# sch.net
KiCad netlist of a schematic drawn in Altium Designer
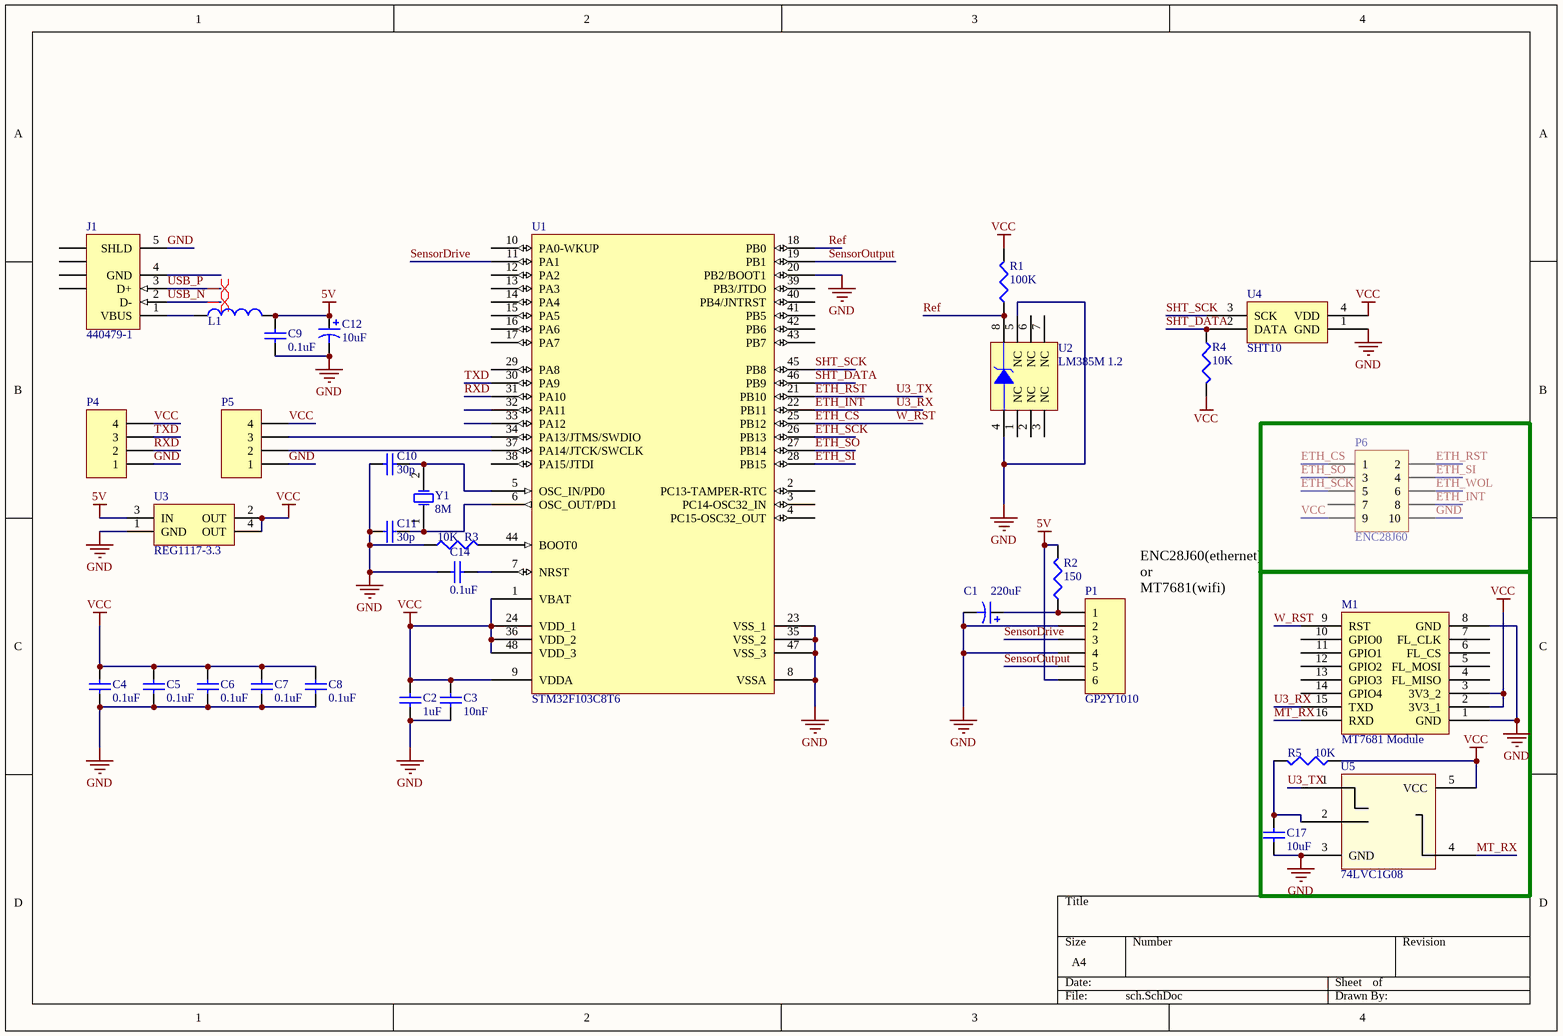
[diagram p0: sch.SchDoc]

(export (version "E")
  (design (tool "Eeschema 10.0.6"))
  (components
    (comp (ref "C1")
      (value "220uF")
      (footprint "B")
      (description "Polarized Capacitor (Radial)")
      (fields (field (name "Comment") "Cap Pol1") (field (name "PUBLISHER") "Altium Limited"))
      (libsource (lib "Miscellaneous Devices") (part "Cap Pol1"))
    )
    (comp (ref "C2")
      (value "1uF")
      (footprint "C1206")
      (description "Capacitor (Semiconductor SIM Model)")
      (fields (field (name "Comment") "Cap Semi") (field (name "PUBLISHER") "Altium Limited"))
      (libsource (lib "Miscellaneous Devices") (part "Cap Semi"))
    )
    (comp (ref "C3")
      (value "10nF")
      (footprint "C1206")
      (description "Capacitor (Semiconductor SIM Model)")
      (fields (field (name "Comment") "Cap Semi") (field (name "PUBLISHER") "Altium Limited"))
      (libsource (lib "Miscellaneous Devices") (part "Cap Semi"))
    )
    (comp (ref "C4")
      (value "0.1uF")
      (footprint "C1206")
      (description "Capacitor (Semiconductor SIM Model)")
      (fields (field (name "Comment") "Cap Semi") (field (name "PUBLISHER") "Altium Limited"))
      (libsource (lib "Miscellaneous Devices") (part "Cap Semi"))
    )
    (comp (ref "C5")
      (value "0.1uF")
      (footprint "C1206")
      (description "Capacitor (Semiconductor SIM Model)")
      (fields (field (name "Comment") "Cap Semi") (field (name "PUBLISHER") "Altium Limited"))
      (libsource (lib "Miscellaneous Devices") (part "Cap Semi"))
    )
    (comp (ref "C6")
      (value "0.1uF")
      (footprint "C1206")
      (description "Capacitor (Semiconductor SIM Model)")
      (fields (field (name "Comment") "Cap Semi") (field (name "PUBLISHER") "Altium Limited"))
      (libsource (lib "Miscellaneous Devices") (part "Cap Semi"))
    )
    (comp (ref "C7")
      (value "0.1uF")
      (footprint "C1206")
      (description "Capacitor (Semiconductor SIM Model)")
      (fields (field (name "Comment") "Cap Semi") (field (name "PUBLISHER") "Altium Limited"))
      (libsource (lib "Miscellaneous Devices") (part "Cap Semi"))
    )
    (comp (ref "C8")
      (value "0.1uF")
      (footprint "C1206")
      (description "Capacitor (Semiconductor SIM Model)")
      (fields (field (name "Comment") "Cap Semi") (field (name "PUBLISHER") "Altium Limited"))
      (libsource (lib "Miscellaneous Devices") (part "Cap Semi"))
    )
    (comp (ref "C9")
      (value "0.1uF")
      (footprint "C1206")
      (description "Capacitor (Semiconductor SIM Model)")
      (fields (field (name "Comment") "Cap Semi") (field (name "PUBLISHER") "Altium Limited"))
      (libsource (lib "Miscellaneous Devices") (part "Cap Semi"))
    )
    (comp (ref "C10")
      (value "30p")
      (footprint "C1206")
      (description "Capacitor (Semiconductor SIM Model)")
      (fields (field (name "Comment") "Cap Semi") (field (name "PUBLISHER") "Altium Limited"))
      (libsource (lib "Miscellaneous Devices") (part "Cap Semi"))
    )
    (comp (ref "C11")
      (value "30p")
      (footprint "C1206")
      (description "Capacitor (Semiconductor SIM Model)")
      (fields (field (name "Comment") "Cap Semi") (field (name "PUBLISHER") "Altium Limited"))
      (libsource (lib "Miscellaneous Devices") (part "Cap Semi"))
    )
    (comp (ref "C12")
      (value "10uF")
      (footprint "1812")
      (description "Polarized Capacitor (Surface Mount)")
      (fields (field (name "Comment") "Cap Pol3") (field (name "PUBLISHER") "Altium Limited"))
      (libsource (lib "Miscellaneous Devices") (part "Cap Pol3"))
    )
    (comp (ref "C14")
      (value "0.1uF")
      (footprint "C1206")
      (description "Capacitor (Semiconductor SIM Model)")
      (fields (field (name "Comment") "Cap Semi") (field (name "PUBLISHER") "Altium Limited"))
      (libsource (lib "Miscellaneous Devices") (part "Cap Semi"))
    )
    (comp (ref "C17")
      (value "10uF")
      (footprint "C1206")
      (description "Capacitor (Semiconductor SIM Model)")
      (fields (field (name "Comment") "Cap Semi") (field (name "PUBLISHER") "Altium Limited"))
      (libsource (lib "Miscellaneous Devices") (part "Cap Semi"))
    )
    (comp (ref "J1")
      (value "440479-1")
      (footprint "440479")
      (description "USB 2.0, Right Angle, SMT, AB Type, Receptacle, 5 Position, Black")
      (fields (field (name "PUBLISHER") "Altium Limited"))
      (libsource (lib "AMP Serial Bus USB") (part "440479-1"))
    )
    (comp (ref "L1")
      (value "Inductor")
      (footprint "2012_Chip")
      (fields (field (name "PUBLISHER") "Altium Limited"))
      (libsource (lib "Miscellaneous Devices") (part "Inductor"))
    )
    (comp (ref "M1") (value "MT7681 Module") (libsource (lib "MT7681_MOD") (part "MT7681")))
    (comp (ref "P1")
      (value "GP2Y1010")
      (footprint "GP2Y1010AU0F")
      (description "Header, 6-Pin")
      (fields (field (name "PUBLISHER") "Altium Limited"))
      (libsource (lib "Miscellaneous Connectors") (part "Header 6"))
    )
    (comp (ref "P4")
      (value "Header 4")
      (footprint "HDR1X4")
      (description "Header, 4-Pin")
      (fields (field (name "PUBLISHER") "Altium Limited"))
      (libsource (lib "Miscellaneous Connectors") (part "Header 4"))
    )
    (comp (ref "P5")
      (value "Header 4")
      (footprint "HDR1X4")
      (description "Header, 4-Pin")
      (fields (field (name "PUBLISHER") "Altium Limited"))
      (libsource (lib "Miscellaneous Connectors") (part "Header 4"))
    )
    (comp (ref "P6")
      (value "ENC28J60")
      (footprint "ENC28J60Board")
      (description "Header, 5-Pin, Dual row")
      (fields (field (name "PUBLISHER") "Altium Limited"))
      (libsource (lib "Miscellaneous Connectors") (part "Header 5X2"))
    )
    (comp (ref "R1")
      (value "100K")
      (footprint "2012[0805]")
      (description "Resistor")
      (fields (field (name "Comment") "Res3") (field (name "PUBLISHER") "Altium Limited"))
      (libsource (lib "Miscellaneous Devices") (part "Res3"))
    )
    (comp (ref "R2")
      (value "150")
      (footprint "2012[0805]")
      (description "Resistor")
      (fields (field (name "Comment") "Res3") (field (name "PUBLISHER") "Altium Limited"))
      (libsource (lib "Miscellaneous Devices") (part "Res3"))
    )
    (comp (ref "R3")
      (value "10K")
      (footprint "2012[0805]")
      (description "Resistor")
      (fields (field (name "Comment") "Res3") (field (name "PUBLISHER") "Altium Limited"))
      (libsource (lib "Miscellaneous Devices") (part "Res3"))
    )
    (comp (ref "R4")
      (value "10K")
      (footprint "2012[0805]")
      (description "Resistor")
      (fields (field (name "Comment") "Res3") (field (name "PUBLISHER") "Altium Limited"))
      (libsource (lib "Miscellaneous Devices") (part "Res3"))
    )
    (comp (ref "R5")
      (value "10K")
      (footprint "2012[0805]")
      (description "Resistor")
      (fields (field (name "Comment") "Res3") (field (name "PUBLISHER") "Altium Limited"))
      (libsource (lib "Miscellaneous Devices") (part "Res3"))
    )
    (comp (ref "U1")
      (value "STM32F103C8T6")
      (footprint "LQFP48_N")
      (description "STM32 ARM-based 32-bit MCU with 64 Kbytes Flash, 48-pin LQFP, Industrial Temperature")
      (fields (field (name "PUBLISHER") "Altium Limited"))
      (libsource (lib "ST Microcontroller 32-Bit STM32") (part "STM32F103C8T6"))
    )
    (comp (ref "U2")
      (value "LM385M 1.2")
      (footprint "D008_N")
      (description "Micropower Voltage Reference")
      (fields (field (name "PUBLISHER") "Altium Limited"))
      (libsource (lib "TI Power Mgt Voltage Reference") (part "LM385D-2.5"))
    )
    (comp (ref "U3")
      (value "REG1117-3.3")
      (footprint "ZZ311")
      (description "800mA and 1A Low Dropout Positive Regulator 2.85V, 3.3V, 5V, and Adjustable")
      (fields (field (name "PUBLISHER") "Altium Limited"))
      (libsource (lib "BB Power Mgt Voltage Regulator") (part "REG1117-3.3"))
    )
    (comp (ref "U4") (value "SHT10") (footprint "SOIC127P600-8N") (libsource (lib "SHT10") (part "SHT10")))
    (comp (ref "U5") (value "74LVC1G08") (libsource (lib "74lvc1g08") (part "74LVC1G08")))
    (comp (ref "Y1")
      (value "8M")
      (footprint "BCY-W2/E4.7")
      (description "Crystal Oscillator")
      (fields (field (name "PUBLISHER") "Altium Limited"))
      (libsource (lib "Miscellaneous Devices") (part "XTAL"))
    )
  )
  (nets
    (net (code "1") (name "/ETH_CS") (class "Default")
      (node (ref "M1") (pin "9") (pinfunction "RST_9") (pintype "passive"))
      (node (ref "P6") (pin "1") (pinfunction "1_1") (pintype "passive"))
      (node (ref "U1") (pin "25") (pinfunction "PB12_25") (pintype "bidirectional"))
    )
    (net (code "2") (name "/ETH_INT") (class "Default")
      (node (ref "M1") (pin "15") (pinfunction "TXD_15") (pintype "passive"))
      (node (ref "P6") (pin "8") (pinfunction "8_8") (pintype "passive"))
      (node (ref "U1") (pin "22") (pinfunction "PB11_22") (pintype "bidirectional"))
    )
    (net (code "3") (name "/ETH_RST") (class "Default")
      (node (ref "P6") (pin "2") (pinfunction "2_2") (pintype "passive"))
      (node (ref "U1") (pin "21") (pinfunction "PB10_21") (pintype "bidirectional"))
      (node (ref "U5") (pin "1") (pinfunction "B_1") (pintype "passive"))
    )
    (net (code "4") (name "/ETH_SCK") (class "Default")
      (node (ref "P6") (pin "5") (pinfunction "5_5") (pintype "passive"))
      (node (ref "U1") (pin "26") (pinfunction "PB13_26") (pintype "bidirectional"))
    )
    (net (code "5") (name "/ETH_SI") (class "Default")
      (node (ref "P6") (pin "4") (pinfunction "4_4") (pintype "passive"))
      (node (ref "U1") (pin "28") (pinfunction "PB15_28") (pintype "bidirectional"))
    )
    (net (code "6") (name "/ETH_SO") (class "Default")
      (node (ref "P6") (pin "3") (pinfunction "3_3") (pintype "passive"))
      (node (ref "U1") (pin "27") (pinfunction "PB14_27") (pintype "bidirectional"))
    )
    (net (code "7") (name "/ETH_WOL") (class "Default")
      (node (ref "P6") (pin "6") (pinfunction "6_6") (pintype "passive"))
    )
    (net (code "8") (name "/MT_RX") (class "Default")
      (node (ref "M1") (pin "16") (pinfunction "RXD_16") (pintype "passive"))
      (node (ref "U5") (pin "4") (pinfunction "Y_4") (pintype "passive"))
    )
    (net (code "9") (name "/RXD") (class "Default")
      (node (ref "P4") (pin "2") (pinfunction "2_2") (pintype "passive"))
      (node (ref "U1") (pin "31") (pinfunction "PA10_31") (pintype "bidirectional"))
    )
    (net (code "10") (name "/Ref") (class "Default")
      (node (ref "R1") (pin "1") (pinfunction "1_1") (pintype "passive"))
      (node (ref "U1") (pin "18") (pinfunction "PB0_18") (pintype "bidirectional"))
      (node (ref "U2") (pin "8") (pinfunction "K_8") (pintype "passive"))
    )
    (net (code "11") (name "/SHT_DATA") (class "Default")
      (node (ref "R4") (pin "1") (pinfunction "1_1") (pintype "passive"))
      (node (ref "U1") (pin "46") (pinfunction "PB9_46") (pintype "bidirectional"))
      (node (ref "U4") (pin "2") (pinfunction "DATA_2") (pintype "passive"))
    )
    (net (code "12") (name "/SHT_SCK") (class "Default")
      (node (ref "U1") (pin "45") (pinfunction "PB8_45") (pintype "bidirectional"))
      (node (ref "U4") (pin "3") (pinfunction "SCK_3") (pintype "passive"))
    )
    (net (code "13") (name "/SensorDrive") (class "Default")
      (node (ref "P1") (pin "3") (pinfunction "3_3") (pintype "passive"))
      (node (ref "U1") (pin "11") (pinfunction "PA1_11") (pintype "bidirectional"))
    )
    (net (code "14") (name "/SensorOutput") (class "Default")
      (node (ref "P1") (pin "5") (pinfunction "5_5") (pintype "passive"))
      (node (ref "U1") (pin "19") (pinfunction "PB1_19") (pintype "bidirectional"))
    )
    (net (code "15") (name "/TXD") (class "Default")
      (node (ref "P4") (pin "3") (pinfunction "3_3") (pintype "passive"))
      (node (ref "U1") (pin "30") (pinfunction "PA9_30") (pintype "bidirectional"))
    )
    (net (code "16") (name "/USB_N") (class "Default")
      (node (ref "J1") (pin "2") (pinfunction "D-_2") (pintype "input"))
    )
    (net (code "17") (name "/USB_P") (class "Default")
      (node (ref "J1") (pin "3") (pinfunction "D+_3") (pintype "input"))
    )
    (net (code "18") (name "5V") (class "Default")
      (node (ref "C12") (pin "1") (pinfunction "1_1") (pintype "passive"))
      (node (ref "C9") (pin "2") (pinfunction "2_2") (pintype "passive"))
      (node (ref "L1") (pin "2") (pinfunction "2_2") (pintype "passive"))
      (node (ref "P1") (pin "6") (pinfunction "6_6") (pintype "passive"))
      (node (ref "R2") (pin "2") (pinfunction "2_2") (pintype "passive"))
      (node (ref "U3") (pin "3") (pinfunction "IN_3") (pintype "power_in"))
    )
    (net (code "19") (name "GND") (class "Default")
      (node (ref "C1") (pin "2") (pinfunction "2_2") (pintype "passive"))
      (node (ref "C10") (pin "2") (pinfunction "2_2") (pintype "passive"))
      (node (ref "C11") (pin "2") (pinfunction "2_2") (pintype "passive"))
      (node (ref "C12") (pin "2") (pinfunction "2_2") (pintype "passive"))
      (node (ref "C14") (pin "2") (pinfunction "2_2") (pintype "passive"))
      (node (ref "C17") (pin "1") (pinfunction "1_1") (pintype "passive"))
      (node (ref "C2") (pin "1") (pinfunction "1_1") (pintype "passive"))
      (node (ref "C3") (pin "1") (pinfunction "1_1") (pintype "passive"))
      (node (ref "C4") (pin "1") (pinfunction "1_1") (pintype "passive"))
      (node (ref "C5") (pin "1") (pinfunction "1_1") (pintype "passive"))
      (node (ref "C6") (pin "1") (pinfunction "1_1") (pintype "passive"))
      (node (ref "C7") (pin "1") (pinfunction "1_1") (pintype "passive"))
      (node (ref "C8") (pin "1") (pinfunction "1_1") (pintype "passive"))
      (node (ref "C9") (pin "1") (pinfunction "1_1") (pintype "passive"))
      (node (ref "J1") (pin "5") (pinfunction "SHLD_5") (pintype "passive"))
      (node (ref "M1") (pin "1") (pinfunction "GND_1") (pintype "passive"))
      (node (ref "M1") (pin "8") (pinfunction "GND_8") (pintype "passive"))
      (node (ref "P1") (pin "2") (pinfunction "2_2") (pintype "passive"))
      (node (ref "P1") (pin "4") (pinfunction "4_4") (pintype "passive"))
      (node (ref "P4") (pin "1") (pinfunction "1_1") (pintype "passive"))
      (node (ref "P5") (pin "1") (pinfunction "1_1") (pintype "passive"))
      (node (ref "P6") (pin "10") (pinfunction "10_10") (pintype "passive"))
      (node (ref "R3") (pin "1") (pinfunction "1_1") (pintype "passive"))
      (node (ref "U1") (pin "20") (pinfunction "PB2/BOOT1_20") (pintype "bidirectional"))
      (node (ref "U1") (pin "23") (pinfunction "VSS_1_23") (pintype "power_in"))
      (node (ref "U1") (pin "35") (pinfunction "VSS_2_35") (pintype "power_in"))
      (node (ref "U1") (pin "47") (pinfunction "VSS_3_47") (pintype "power_in"))
      (node (ref "U1") (pin "8") (pinfunction "VSSA_8") (pintype "power_in"))
      (node (ref "U2") (pin "4") (pinfunction "A_4") (pintype "passive"))
      (node (ref "U2") (pin "5") (pinfunction "NC_5") (pintype "passive"))
      (node (ref "U3") (pin "1") (pinfunction "GND_1") (pintype "power_in"))
      (node (ref "U4") (pin "1") (pinfunction "GND_1") (pintype "passive"))
      (node (ref "U5") (pin "3") (pinfunction "GND_3") (pintype "passive"))
    )
    (net (code "20") (name "Net-(C1-Pad1)") (class "Default")
      (node (ref "C1") (pin "1") (pinfunction "1_1") (pintype "passive"))
      (node (ref "P1") (pin "1") (pinfunction "1_1") (pintype "passive"))
      (node (ref "R2") (pin "1") (pinfunction "1_1") (pintype "passive"))
    )
    (net (code "21") (name "Net-(J1-VBUS)") (class "Default")
      (node (ref "J1") (pin "1") (pinfunction "VBUS_1") (pintype "power_in"))
      (node (ref "L1") (pin "1") (pinfunction "1_1") (pintype "passive"))
    )
    (net (code "22") (name "Net-(U1-BOOT0)") (class "Default")
      (node (ref "R3") (pin "2") (pinfunction "2_2") (pintype "passive"))
      (node (ref "U1") (pin "44") (pinfunction "BOOT0_44") (pintype "input"))
    )
    (net (code "23") (name "Net-(U1-NRST)") (class "Default")
      (node (ref "C14") (pin "1") (pinfunction "1_1") (pintype "passive"))
      (node (ref "U1") (pin "7") (pinfunction "NRST_7") (pintype "bidirectional"))
    )
    (net (code "24") (name "Net-(U1-OSC_IN{slash}PD0)") (class "Default")
      (node (ref "C10") (pin "1") (pinfunction "1_1") (pintype "passive"))
      (node (ref "U1") (pin "5") (pinfunction "OSC_IN/PD0_5") (pintype "input"))
      (node (ref "Y1") (pin "2") (pinfunction "OSC2_2") (pintype "passive"))
    )
    (net (code "25") (name "Net-(U1-OSC_OUT{slash}PD1)") (class "Default")
      (node (ref "C11") (pin "1") (pinfunction "1_1") (pintype "passive"))
      (node (ref "U1") (pin "6") (pinfunction "OSC_OUT/PD1_6") (pintype "output"))
      (node (ref "Y1") (pin "1") (pinfunction "OSC1_1") (pintype "passive"))
    )
    (net (code "26") (name "Net-(U1-PA13{slash}JTMS{slash}SWDIO)") (class "Default")
      (node (ref "P5") (pin "3") (pinfunction "3_3") (pintype "passive"))
      (node (ref "U1") (pin "34") (pinfunction "PA13/JTMS/SWDIO_34") (pintype "bidirectional"))
    )
    (net (code "27") (name "Net-(U1-PA14{slash}JTCK{slash}SWCLK)") (class "Default")
      (node (ref "P5") (pin "2") (pinfunction "2_2") (pintype "passive"))
      (node (ref "U1") (pin "37") (pinfunction "PA14/JTCK/SWCLK_37") (pintype "bidirectional"))
    )
    (net (code "28") (name "Net-(U5-A)") (class "Default")
      (node (ref "C17") (pin "2") (pinfunction "2_2") (pintype "passive"))
      (node (ref "R5") (pin "2") (pinfunction "2_2") (pintype "passive"))
      (node (ref "U5") (pin "2") (pinfunction "A_2") (pintype "passive"))
    )
    (net (code "29") (name "VCC") (class "Default")
      (node (ref "C2") (pin "2") (pinfunction "2_2") (pintype "passive"))
      (node (ref "C3") (pin "2") (pinfunction "2_2") (pintype "passive"))
      (node (ref "C4") (pin "2") (pinfunction "2_2") (pintype "passive"))
      (node (ref "C5") (pin "2") (pinfunction "2_2") (pintype "passive"))
      (node (ref "C6") (pin "2") (pinfunction "2_2") (pintype "passive"))
      (node (ref "C7") (pin "2") (pinfunction "2_2") (pintype "passive"))
      (node (ref "C8") (pin "2") (pinfunction "2_2") (pintype "passive"))
      (node (ref "M1") (pin "2") (pinfunction "3V3_1_2") (pintype "passive"))
      (node (ref "M1") (pin "3") (pinfunction "3V3_2_3") (pintype "passive"))
      (node (ref "P4") (pin "4") (pinfunction "4_4") (pintype "passive"))
      (node (ref "P5") (pin "4") (pinfunction "4_4") (pintype "passive"))
      (node (ref "P6") (pin "9") (pinfunction "9_9") (pintype "passive"))
      (node (ref "R1") (pin "2") (pinfunction "2_2") (pintype "passive"))
      (node (ref "R4") (pin "2") (pinfunction "2_2") (pintype "passive"))
      (node (ref "R5") (pin "1") (pinfunction "1_1") (pintype "passive"))
      (node (ref "U1") (pin "1") (pinfunction "VBAT_1") (pintype "power_in"))
      (node (ref "U1") (pin "24") (pinfunction "VDD_1_24") (pintype "power_in"))
      (node (ref "U1") (pin "36") (pinfunction "VDD_2_36") (pintype "power_in"))
      (node (ref "U1") (pin "48") (pinfunction "VDD_3_48") (pintype "power_in"))
      (node (ref "U1") (pin "9") (pinfunction "VDDA_9") (pintype "power_in"))
      (node (ref "U3") (pin "2") (pinfunction "OUT_2") (pintype "power_in"))
      (node (ref "U3") (pin "4") (pinfunction "OUT_4") (pintype "power_in"))
      (node (ref "U4") (pin "4") (pinfunction "VDD_4") (pintype "passive"))
      (node (ref "U5") (pin "5") (pinfunction "VCC_5") (pintype "passive"))
    )
    (net (code "30") (name "unconnected-(J1-GND-Pad4)") (class "Default")
      (node (ref "J1") (pin "4") (pinfunction "GND_4") (pintype "power_in"))
    )
    (net (code "31") (name "unconnected-(J1-SHLD-Pad6)") (class "Default")
      (node (ref "J1") (pin "6") (pinfunction "SHLD_6") (pintype "passive"))
    )
    (net (code "32") (name "unconnected-(J1-SHLD-Pad7)") (class "Default")
      (node (ref "J1") (pin "7") (pinfunction "SHLD_7") (pintype "passive"))
    )
    (net (code "33") (name "unconnected-(J1-SHLD-Pad8)") (class "Default")
      (node (ref "J1") (pin "8") (pinfunction "SHLD_8") (pintype "passive"))
    )
    (net (code "34") (name "unconnected-(J1-SHLD-Pad9)") (class "Default")
      (node (ref "J1") (pin "9") (pinfunction "SHLD_9") (pintype "passive"))
    )
    (net (code "35") (name "unconnected-(M1-FL_CLK-Pad7)") (class "Default")
      (node (ref "M1") (pin "7") (pinfunction "FL_CLK_7") (pintype "passive"))
    )
    (net (code "36") (name "unconnected-(M1-FL_CS-Pad6)") (class "Default")
      (node (ref "M1") (pin "6") (pinfunction "FL_CS_6") (pintype "passive"))
    )
    (net (code "37") (name "unconnected-(M1-FL_MISO-Pad4)") (class "Default")
      (node (ref "M1") (pin "4") (pinfunction "FL_MISO_4") (pintype "passive"))
    )
    (net (code "38") (name "unconnected-(M1-FL_MOSI-Pad5)") (class "Default")
      (node (ref "M1") (pin "5") (pinfunction "FL_MOSI_5") (pintype "passive"))
    )
    (net (code "39") (name "unconnected-(M1-GPIO0-Pad10)") (class "Default")
      (node (ref "M1") (pin "10") (pinfunction "GPIO0_10") (pintype "passive"))
    )
    (net (code "40") (name "unconnected-(M1-GPIO1-Pad11)") (class "Default")
      (node (ref "M1") (pin "11") (pinfunction "GPIO1_11") (pintype "passive"))
    )
    (net (code "41") (name "unconnected-(M1-GPIO2-Pad12)") (class "Default")
      (node (ref "M1") (pin "12") (pinfunction "GPIO2_12") (pintype "passive"))
    )
    (net (code "42") (name "unconnected-(M1-GPIO3-Pad13)") (class "Default")
      (node (ref "M1") (pin "13") (pinfunction "GPIO3_13") (pintype "passive"))
    )
    (net (code "43") (name "unconnected-(M1-GPIO4-Pad14)") (class "Default")
      (node (ref "M1") (pin "14") (pinfunction "GPIO4_14") (pintype "passive"))
    )
    (net (code "44") (name "unconnected-(P6-Pad7)") (class "Default")
      (node (ref "P6") (pin "7") (pinfunction "7_7") (pintype "passive"))
    )
    (net (code "45") (name "unconnected-(U1-PA0-WKUP-Pad10)") (class "Default")
      (node (ref "U1") (pin "10") (pinfunction "PA0-WKUP_10") (pintype "bidirectional"))
    )
    (net (code "46") (name "unconnected-(U1-PA2-Pad12)") (class "Default")
      (node (ref "U1") (pin "12") (pinfunction "PA2_12") (pintype "bidirectional"))
    )
    (net (code "47") (name "unconnected-(U1-PA3-Pad13)") (class "Default")
      (node (ref "U1") (pin "13") (pinfunction "PA3_13") (pintype "bidirectional"))
    )
    (net (code "48") (name "unconnected-(U1-PA4-Pad14)") (class "Default")
      (node (ref "U1") (pin "14") (pinfunction "PA4_14") (pintype "bidirectional"))
    )
    (net (code "49") (name "unconnected-(U1-PA5-Pad15)") (class "Default")
      (node (ref "U1") (pin "15") (pinfunction "PA5_15") (pintype "bidirectional"))
    )
    (net (code "50") (name "unconnected-(U1-PA6-Pad16)") (class "Default")
      (node (ref "U1") (pin "16") (pinfunction "PA6_16") (pintype "bidirectional"))
    )
    (net (code "51") (name "unconnected-(U1-PA7-Pad17)") (class "Default")
      (node (ref "U1") (pin "17") (pinfunction "PA7_17") (pintype "bidirectional"))
    )
    (net (code "52") (name "unconnected-(U1-PA8-Pad29)") (class "Default")
      (node (ref "U1") (pin "29") (pinfunction "PA8_29") (pintype "bidirectional"))
    )
    (net (code "53") (name "unconnected-(U1-PA11-Pad32)") (class "Default")
      (node (ref "U1") (pin "32") (pinfunction "PA11_32") (pintype "bidirectional"))
    )
    (net (code "54") (name "unconnected-(U1-PA12-Pad33)") (class "Default")
      (node (ref "U1") (pin "33") (pinfunction "PA12_33") (pintype "bidirectional"))
    )
    (net (code "55") (name "unconnected-(U1-PA15{slash}JTDI-Pad38)") (class "Default")
      (node (ref "U1") (pin "38") (pinfunction "PA15/JTDI_38") (pintype "bidirectional"))
    )
    (net (code "56") (name "unconnected-(U1-PB3{slash}JTDO-Pad39)") (class "Default")
      (node (ref "U1") (pin "39") (pinfunction "PB3/JTDO_39") (pintype "bidirectional"))
    )
    (net (code "57") (name "unconnected-(U1-PB4{slash}JNTRST-Pad40)") (class "Default")
      (node (ref "U1") (pin "40") (pinfunction "PB4/JNTRST_40") (pintype "bidirectional"))
    )
    (net (code "58") (name "unconnected-(U1-PB5-Pad41)") (class "Default")
      (node (ref "U1") (pin "41") (pinfunction "PB5_41") (pintype "bidirectional"))
    )
    (net (code "59") (name "unconnected-(U1-PB6-Pad42)") (class "Default")
      (node (ref "U1") (pin "42") (pinfunction "PB6_42") (pintype "bidirectional"))
    )
    (net (code "60") (name "unconnected-(U1-PB7-Pad43)") (class "Default")
      (node (ref "U1") (pin "43") (pinfunction "PB7_43") (pintype "bidirectional"))
    )
    (net (code "61") (name "unconnected-(U1-PC13-TAMPER-RTC-Pad2)") (class "Default")
      (node (ref "U1") (pin "2") (pinfunction "PC13-TAMPER-RTC_2") (pintype "bidirectional"))
    )
    (net (code "62") (name "unconnected-(U1-PC14-OSC32_IN-Pad3)") (class "Default")
      (node (ref "U1") (pin "3") (pinfunction "PC14-OSC32_IN_3") (pintype "bidirectional"))
    )
    (net (code "63") (name "unconnected-(U1-PC15-OSC32_OUT-Pad4)") (class "Default")
      (node (ref "U1") (pin "4") (pinfunction "PC15-OSC32_OUT_4") (pintype "bidirectional"))
    )
    (net (code "64") (name "unconnected-(U2-NC-Pad1)") (class "Default")
      (node (ref "U2") (pin "1") (pinfunction "NC_1") (pintype "passive"))
    )
    (net (code "65") (name "unconnected-(U2-NC-Pad2)") (class "Default")
      (node (ref "U2") (pin "2") (pinfunction "NC_2") (pintype "passive"))
    )
    (net (code "66") (name "unconnected-(U2-NC-Pad3)") (class "Default")
      (node (ref "U2") (pin "3") (pinfunction "NC_3") (pintype "passive"))
    )
    (net (code "67") (name "unconnected-(U2-NC-Pad6)") (class "Default")
      (node (ref "U2") (pin "6") (pinfunction "NC_6") (pintype "passive"))
    )
    (net (code "68") (name "unconnected-(U2-NC-Pad7)") (class "Default")
      (node (ref "U2") (pin "7") (pinfunction "NC_7") (pintype "passive"))
    )
  )
)
